# Schematic_MotherBoard.net
KiCad netlist of a schematic drawn in Altium Designer
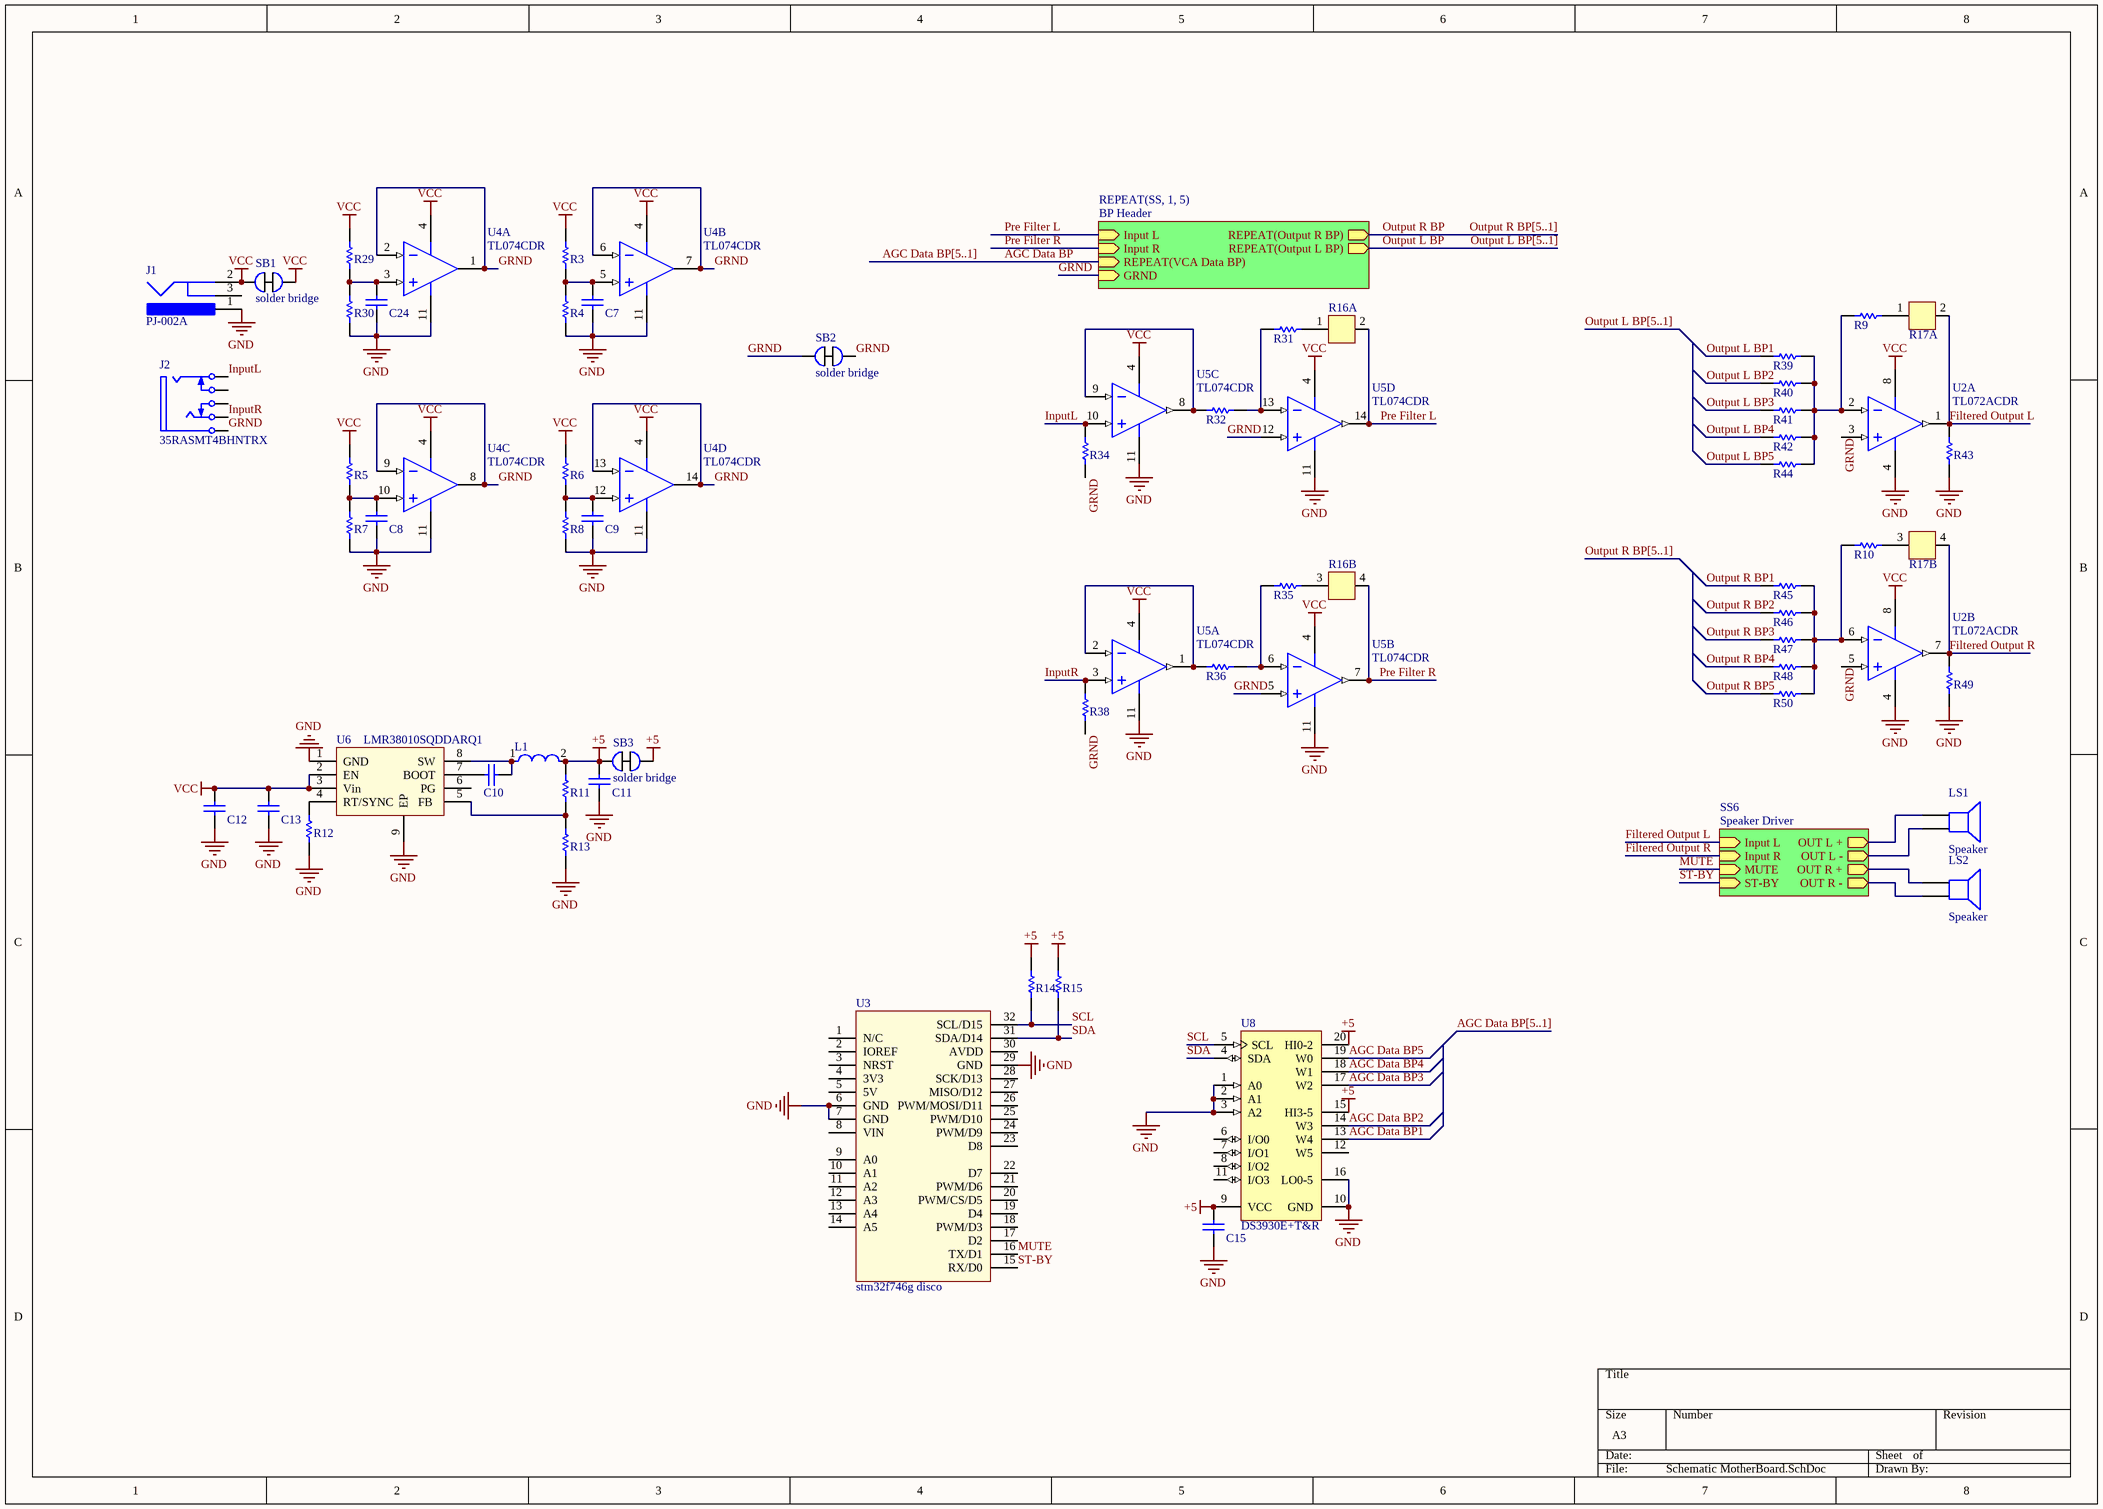
[diagram p0: Schematic MotherBoard.SchDoc]

(export (version "E")
  (design (tool "Eeschema 10.0.6"))
  (components
    (comp (ref "C7")
      (value "1206GC102KAT1A")
      (footprint "AVX-1206-2_L")
      (description "Chip Capacitor, 1 nF, +/- 10%, -55 to 125 degC, 1206 (3216 Metric), RoHS, Tape and Reel")
      (fields (field (name "TOLERANCE") "10%") (field (name "MANUFACTURER") "AVX"))
      (libsource (lib "Altium Content Vault") (part "CAP-NP-2"))
    )
    (comp (ref "C8")
      (value "1206GC102KAT1A")
      (footprint "AVX-1206-2_L")
      (description "Chip Capacitor, 1 nF, +/- 10%, -55 to 125 degC, 1206 (3216 Metric), RoHS, Tape and Reel")
      (fields (field (name "TOLERANCE") "10%") (field (name "MANUFACTURER") "AVX"))
      (libsource (lib "Altium Content Vault") (part "CAP-NP-2"))
    )
    (comp (ref "C9")
      (value "1206GC102KAT1A")
      (footprint "AVX-1206-2_L")
      (description "Chip Capacitor, 1 nF, +/- 10%, -55 to 125 degC, 1206 (3216 Metric), RoHS, Tape and Reel")
      (fields (field (name "TOLERANCE") "10%") (field (name "MANUFACTURER") "AVX"))
      (libsource (lib "Altium Content Vault") (part "CAP-NP-2"))
    )
    (comp (ref "C10")
      (value "1206GC102KAT1A")
      (footprint "AVX-1206-2_L")
      (description "Chip Capacitor, 1 nF, +/- 10%, -55 to 125 degC, 1206 (3216 Metric), RoHS, Tape and Reel")
      (fields (field (name "TOLERANCE") "10%") (field (name "MANUFACTURER") "AVX"))
      (libsource (lib "Altium Content Vault") (part "CAP-NP-2"))
    )
    (comp (ref "C11")
      (value "1206GC102KAT1A")
      (footprint "AVX-1206-2_L")
      (description "Chip Capacitor, 1 nF, +/- 10%, -55 to 125 degC, 1206 (3216 Metric), RoHS, Tape and Reel")
      (fields (field (name "TOLERANCE") "10%") (field (name "MANUFACTURER") "AVX"))
      (libsource (lib "Altium Content Vault") (part "CAP-NP-2"))
    )
    (comp (ref "C12")
      (value "1206GC102KAT1A")
      (footprint "AVX-1206-2_L")
      (description "Chip Capacitor, 1 nF, +/- 10%, -55 to 125 degC, 1206 (3216 Metric), RoHS, Tape and Reel")
      (fields (field (name "TOLERANCE") "10%") (field (name "MANUFACTURER") "AVX"))
      (libsource (lib "Altium Content Vault") (part "CAP-NP-2"))
    )
    (comp (ref "C13")
      (value "1206GC102KAT1A")
      (footprint "AVX-1206-2_L")
      (description "Chip Capacitor, 1 nF, +/- 10%, -55 to 125 degC, 1206 (3216 Metric), RoHS, Tape and Reel")
      (fields (field (name "TOLERANCE") "10%") (field (name "MANUFACTURER") "AVX"))
      (libsource (lib "Altium Content Vault") (part "CAP-NP-2"))
    )
    (comp (ref "C15")
      (value "1206GC102KAT1A")
      (footprint "AVX-1206-2_L")
      (description "Chip Capacitor, 1 nF, +/- 10%, -55 to 125 degC, 1206 (3216 Metric), RoHS, Tape and Reel")
      (fields (field (name "TOLERANCE") "10%") (field (name "MANUFACTURER") "AVX"))
      (libsource (lib "Altium Content Vault") (part "CAP-NP-2"))
    )
    (comp (ref "C24")
      (value "1206GC102KAT1A")
      (footprint "AVX-1206-2_L")
      (description "Chip Capacitor, 1 nF, +/- 10%, -55 to 125 degC, 1206 (3216 Metric), RoHS, Tape and Reel")
      (fields (field (name "TOLERANCE") "10%") (field (name "MANUFACTURER") "AVX"))
      (libsource (lib "Altium Content Vault") (part "CAP-NP-2"))
    )
    (comp (ref "J1")
      (value "PJ-002A")
      (footprint "CUI-PJ-002A_V")
      (fields (field (name "MANUFACTURER") "CUIInc."))
      (libsource (lib "Altium Content Vault") (part "JACK-2CD3-RN_B"))
    )
    (comp (ref "J2")
      (value "35RASMT4BHNTRX")
      (footprint "SWIT-35RASMT4BHNTRX_V")
      (description "Female 3.5 mm Phone Jack, 5 Position, Height 5 mm, RoHS, Tape and Reel")
      (libsource (lib "Altium Content Vault") (part "JACK-3CD5-RN"))
    )
    (comp (ref "L1")
      (value "IHLP5050EZERR56M01")
      (footprint "FP-IHLP-5050EZ-FP_3_226x4-MFG")
      (description "Commercial Inductors, High Saturation Series 0.56uH 36A 1.5mΩ 20%")
      (fields (field (name "TOLERANCE") "20%"))
      (libsource (lib "Altium Content Vault") (part "725321dda6339637d4d059423bc1c3c"))
    )
    (comp (ref "LS1")
      (value "Speaker")
      (footprint "PIN2")
      (description "Loudspeaker")
      (fields (field (name "PUBLISHER") "Altium Limited"))
      (libsource (lib "Miscellaneous Devices") (part "Speaker"))
    )
    (comp (ref "LS2")
      (value "Speaker")
      (footprint "PIN2")
      (description "Loudspeaker")
      (fields (field (name "PUBLISHER") "Altium Limited"))
      (libsource (lib "Miscellaneous Devices") (part "Speaker"))
    )
    (comp (ref "R3")
      (value "ERJ-8GEY0R00V")
      (footprint "RESC3216X70X50NL05T20")
      (fields (field (name "MANUFACTURER") "Panasonic"))
      (libsource (lib "Altium Content Vault") (part "RES"))
    )
    (comp (ref "R4")
      (value "ERJ-8GEY0R00V")
      (footprint "RESC3216X70X50NL05T20")
      (fields (field (name "MANUFACTURER") "Panasonic"))
      (libsource (lib "Altium Content Vault") (part "RES"))
    )
    (comp (ref "R5")
      (value "ERJ-8GEY0R00V")
      (footprint "RESC3216X70X50NL05T20")
      (fields (field (name "MANUFACTURER") "Panasonic"))
      (libsource (lib "Altium Content Vault") (part "RES"))
    )
    (comp (ref "R6")
      (value "ERJ-8GEY0R00V")
      (footprint "RESC3216X70X50NL05T20")
      (fields (field (name "MANUFACTURER") "Panasonic"))
      (libsource (lib "Altium Content Vault") (part "RES"))
    )
    (comp (ref "R7")
      (value "ERJ-8GEY0R00V")
      (footprint "RESC3216X70X50NL05T20")
      (fields (field (name "MANUFACTURER") "Panasonic"))
      (libsource (lib "Altium Content Vault") (part "RES"))
    )
    (comp (ref "R8")
      (value "ERJ-8GEY0R00V")
      (footprint "RESC3216X70X50NL05T20")
      (fields (field (name "MANUFACTURER") "Panasonic"))
      (libsource (lib "Altium Content Vault") (part "RES"))
    )
    (comp (ref "R9")
      (value "ERJ-8GEY0R00V")
      (footprint "RESC3216X70X50NL05T20")
      (fields (field (name "MANUFACTURER") "Panasonic"))
      (libsource (lib "Altium Content Vault") (part "RES"))
    )
    (comp (ref "R10")
      (value "ERJ-8GEY0R00V")
      (footprint "RESC3216X70X50NL05T20")
      (fields (field (name "MANUFACTURER") "Panasonic"))
      (libsource (lib "Altium Content Vault") (part "RES"))
    )
    (comp (ref "R11")
      (value "ERJ-8GEY0R00V")
      (footprint "RESC3216X70X50NL05T20")
      (fields (field (name "MANUFACTURER") "Panasonic"))
      (libsource (lib "Altium Content Vault") (part "RES"))
    )
    (comp (ref "R12")
      (value "ERJ-8GEY0R00V")
      (footprint "RESC3216X70X50NL05T20")
      (fields (field (name "MANUFACTURER") "Panasonic"))
      (libsource (lib "Altium Content Vault") (part "RES"))
    )
    (comp (ref "R13")
      (value "ERJ-8GEY0R00V")
      (footprint "RESC3216X70X50NL05T20")
      (fields (field (name "MANUFACTURER") "Panasonic"))
      (libsource (lib "Altium Content Vault") (part "RES"))
    )
    (comp (ref "R14")
      (value "ERJ-8GEY0R00V")
      (footprint "RESC3216X70X50NL05T20")
      (fields (field (name "MANUFACTURER") "Panasonic"))
      (libsource (lib "Altium Content Vault") (part "RES"))
    )
    (comp (ref "R15")
      (value "ERJ-8GEY0R00V")
      (footprint "RESC3216X70X50NL05T20")
      (fields (field (name "MANUFACTURER") "Panasonic"))
      (libsource (lib "Altium Content Vault") (part "RES"))
    )
    (comp (ref "R16")
      (value "Pot probes")
      (footprint "Pot probe")
      (libsource (lib "Schlib") (part "Pot probes"))
    )
    (comp (ref "R17")
      (value "Pot probes")
      (footprint "Pot probe")
      (libsource (lib "Schlib") (part "Pot probes"))
    )
    (comp (ref "R29")
      (value "ERJ-8GEY0R00V")
      (footprint "RESC3216X70X50NL05T20")
      (fields (field (name "MANUFACTURER") "Panasonic"))
      (libsource (lib "Altium Content Vault") (part "RES"))
    )
    (comp (ref "R30")
      (value "ERJ-8GEY0R00V")
      (footprint "RESC3216X70X50NL05T20")
      (fields (field (name "MANUFACTURER") "Panasonic"))
      (libsource (lib "Altium Content Vault") (part "RES"))
    )
    (comp (ref "R31")
      (value "ERJ-8GEY0R00V")
      (footprint "RESC3216X70X50NL05T20")
      (fields (field (name "MANUFACTURER") "Panasonic"))
      (libsource (lib "Altium Content Vault") (part "RES"))
    )
    (comp (ref "R32")
      (value "ERJ-8GEY0R00V")
      (footprint "RESC3216X70X50NL05T20")
      (fields (field (name "MANUFACTURER") "Panasonic"))
      (libsource (lib "Altium Content Vault") (part "RES"))
    )
    (comp (ref "R34")
      (value "ERJ-8GEY0R00V")
      (footprint "RESC3216X70X50NL05T20")
      (fields (field (name "MANUFACTURER") "Panasonic"))
      (libsource (lib "Altium Content Vault") (part "RES"))
    )
    (comp (ref "R35")
      (value "ERJ-8GEY0R00V")
      (footprint "RESC3216X70X50NL05T20")
      (fields (field (name "MANUFACTURER") "Panasonic"))
      (libsource (lib "Altium Content Vault") (part "RES"))
    )
    (comp (ref "R36")
      (value "ERJ-8GEY0R00V")
      (footprint "RESC3216X70X50NL05T20")
      (fields (field (name "MANUFACTURER") "Panasonic"))
      (libsource (lib "Altium Content Vault") (part "RES"))
    )
    (comp (ref "R38")
      (value "ERJ-8GEY0R00V")
      (footprint "RESC3216X70X50NL05T20")
      (fields (field (name "MANUFACTURER") "Panasonic"))
      (libsource (lib "Altium Content Vault") (part "RES"))
    )
    (comp (ref "R39")
      (value "ERJ-8GEY0R00V")
      (footprint "RESC3216X70X50NL05T20")
      (fields (field (name "MANUFACTURER") "Panasonic"))
      (libsource (lib "Altium Content Vault") (part "RES"))
    )
    (comp (ref "R40")
      (value "ERJ-8GEY0R00V")
      (footprint "RESC3216X70X50NL05T20")
      (fields (field (name "MANUFACTURER") "Panasonic"))
      (libsource (lib "Altium Content Vault") (part "RES"))
    )
    (comp (ref "R41")
      (value "ERJ-8GEY0R00V")
      (footprint "RESC3216X70X50NL05T20")
      (fields (field (name "MANUFACTURER") "Panasonic"))
      (libsource (lib "Altium Content Vault") (part "RES"))
    )
    (comp (ref "R42")
      (value "ERJ-8GEY0R00V")
      (footprint "RESC3216X70X50NL05T20")
      (fields (field (name "MANUFACTURER") "Panasonic"))
      (libsource (lib "Altium Content Vault") (part "RES"))
    )
    (comp (ref "R43")
      (value "ERJ-8GEY0R00V")
      (footprint "RESC3216X70X50NL05T20")
      (fields (field (name "MANUFACTURER") "Panasonic"))
      (libsource (lib "Altium Content Vault") (part "RES"))
    )
    (comp (ref "R44")
      (value "ERJ-8GEY0R00V")
      (footprint "RESC3216X70X50NL05T20")
      (fields (field (name "MANUFACTURER") "Panasonic"))
      (libsource (lib "Altium Content Vault") (part "RES"))
    )
    (comp (ref "R45")
      (value "ERJ-8GEY0R00V")
      (footprint "RESC3216X70X50NL05T20")
      (fields (field (name "MANUFACTURER") "Panasonic"))
      (libsource (lib "Altium Content Vault") (part "RES"))
    )
    (comp (ref "R46")
      (value "ERJ-8GEY0R00V")
      (footprint "RESC3216X70X50NL05T20")
      (fields (field (name "MANUFACTURER") "Panasonic"))
      (libsource (lib "Altium Content Vault") (part "RES"))
    )
    (comp (ref "R47")
      (value "ERJ-8GEY0R00V")
      (footprint "RESC3216X70X50NL05T20")
      (fields (field (name "MANUFACTURER") "Panasonic"))
      (libsource (lib "Altium Content Vault") (part "RES"))
    )
    (comp (ref "R48")
      (value "ERJ-8GEY0R00V")
      (footprint "RESC3216X70X50NL05T20")
      (fields (field (name "MANUFACTURER") "Panasonic"))
      (libsource (lib "Altium Content Vault") (part "RES"))
    )
    (comp (ref "R49")
      (value "ERJ-8GEY0R00V")
      (footprint "RESC3216X70X50NL05T20")
      (fields (field (name "MANUFACTURER") "Panasonic"))
      (libsource (lib "Altium Content Vault") (part "RES"))
    )
    (comp (ref "R50")
      (value "ERJ-8GEY0R00V")
      (footprint "RESC3216X70X50NL05T20")
      (fields (field (name "MANUFACTURER") "Panasonic"))
      (libsource (lib "Altium Content Vault") (part "RES"))
    )
    (comp (ref "SB1")
      (value "solder bridge")
      (footprint "solder bridge")
      (libsource (lib "Schlib") (part "solder bridge"))
    )
    (comp (ref "SB2")
      (value "solder bridge")
      (footprint "solder bridge")
      (libsource (lib "Schlib") (part "solder bridge"))
    )
    (comp (ref "SB3")
      (value "solder bridge")
      (footprint "solder bridge")
      (libsource (lib "Schlib") (part "solder bridge"))
    )
    (comp (ref "U2")
      (value "TL072ACDR")
      (footprint "D0008A_M")
      (fields (field (name "MANUFACTURER") "Texas Instruments"))
      (libsource (lib "Altium Content Vault") (part "TI-AMP-D6-2-8_D"))
    )
    (comp (ref "U3")
      (value "stm32f746g disco")
      (footprint "stm32f746g disco")
      (libsource (lib "Schlib") (part "stm32f746g disco"))
    )
    (comp (ref "U4")
      (value "TL074CDR")
      (footprint "D0014A_N")
      (fields (field (name "MANUFACTURER") "Texas Instruments"))
      (libsource (lib "Altium Content Vault") (part "TI-TLXX4X_MC3403-X14"))
    )
    (comp (ref "U5")
      (value "TL074CDR")
      (footprint "D0014A_N")
      (fields (field (name "MANUFACTURER") "Texas Instruments"))
      (libsource (lib "Altium Content Vault") (part "TI-TLXX4X_MC3403-X14"))
    )
    (comp (ref "U6")
      (value "LMR38010SQDDARQ1")
      (footprint "LMR38010SQDDARQ1")
      (libsource (lib "Schlib") (part "LMR38010SQDDARQ1"))
    )
    (comp (ref "U8")
      (value "DS3930E+T&R")
      (footprint "MAXM-U20+5_L")
      (libsource (lib "Altium Content Vault") (part "DS3930-U20X5"))
    )
  )
  (nets
    (net (code "1") (name "+5") (class "Default")
      (node (ref "C11") (pin "2") (pinfunction "2_2") (pintype "passive"))
      (node (ref "C15") (pin "2") (pinfunction "2_2") (pintype "passive"))
      (node (ref "L1") (pin "2") (pinfunction "2_2") (pintype "passive"))
      (node (ref "R11") (pin "2") (pinfunction "2_2") (pintype "passive"))
      (node (ref "R14") (pin "2") (pinfunction "2_2") (pintype "passive"))
      (node (ref "R15") (pin "2") (pinfunction "2_2") (pintype "passive"))
      (node (ref "SB3") (pin "1") (pinfunction "1_1") (pintype "passive"))
      (node (ref "SB3") (pin "2") (pinfunction "2_2") (pintype "passive"))
      (node (ref "U8") (pin "15") (pinfunction "HI3-5_15") (pintype "passive"))
      (node (ref "U8") (pin "20") (pinfunction "HI0-2_20") (pintype "passive"))
      (node (ref "U8") (pin "9") (pinfunction "VCC_9") (pintype "power_in"))
    )
    (net (code "3") (name "/AGC Data BP1") (class "Default")
      (node (ref "U8") (pin "13") (pinfunction "W4_13") (pintype "passive"))
    )
    (net (code "4") (name "/AGC Data BP2") (class "Default")
      (node (ref "U8") (pin "14") (pinfunction "W3_14") (pintype "passive"))
    )
    (net (code "5") (name "/AGC Data BP3") (class "Default")
      (node (ref "U8") (pin "17") (pinfunction "W2_17") (pintype "passive"))
    )
    (net (code "6") (name "/AGC Data BP4") (class "Default")
      (node (ref "U8") (pin "18") (pinfunction "W1_18") (pintype "passive"))
    )
    (net (code "7") (name "/AGC Data BP5") (class "Default")
      (node (ref "U8") (pin "19") (pinfunction "W0_19") (pintype "passive"))
    )
    (net (code "8") (name "/Filtered Output L") (class "Default")
      (node (ref "R17") (pin "2") (pinfunction "2_2") (pintype "passive"))
      (node (ref "R43") (pin "1") (pinfunction "1_1") (pintype "passive"))
      (node (ref "U2") (pin "1") (pinfunction "OUT1_1") (pintype "output"))
    )
    (net (code "9") (name "/Filtered Output R") (class "Default")
      (node (ref "R17") (pin "4") (pinfunction "4_4") (pintype "passive"))
      (node (ref "R49") (pin "1") (pinfunction "1_1") (pintype "passive"))
      (node (ref "U2") (pin "7") (pinfunction "OUT2_7") (pintype "output"))
    )
    (net (code "10") (name "/GRND") (class "Default")
      (node (ref "J2") (pin "1") (pinfunction "1_1") (pintype "passive"))
      (node (ref "R34") (pin "2") (pinfunction "2_2") (pintype "passive"))
      (node (ref "R38") (pin "2") (pinfunction "2_2") (pintype "passive"))
      (node (ref "SB2") (pin "1") (pinfunction "1_1") (pintype "passive"))
      (node (ref "SB2") (pin "2") (pinfunction "2_2") (pintype "passive"))
      (node (ref "U2") (pin "3") (pinfunction "IN1+_3") (pintype "input"))
      (node (ref "U2") (pin "5") (pinfunction "IN2+_5") (pintype "input"))
      (node (ref "U4") (pin "1") (pinfunction "OUT1_1") (pintype "output"))
      (node (ref "U4") (pin "13") (pinfunction "IN4-_13") (pintype "input"))
      (node (ref "U4") (pin "14") (pinfunction "OUT4_14") (pintype "output"))
      (node (ref "U4") (pin "2") (pinfunction "IN1-_2") (pintype "input"))
      (node (ref "U4") (pin "6") (pinfunction "IN2-_6") (pintype "input"))
      (node (ref "U4") (pin "7") (pinfunction "OUT2_7") (pintype "output"))
      (node (ref "U4") (pin "8") (pinfunction "OUT3_8") (pintype "output"))
      (node (ref "U4") (pin "9") (pinfunction "IN3-_9") (pintype "input"))
      (node (ref "U5") (pin "12") (pinfunction "IN4+_12") (pintype "input"))
      (node (ref "U5") (pin "5") (pinfunction "IN2+_5") (pintype "input"))
    )
    (net (code "11") (name "/InputL") (class "Default")
      (node (ref "J2") (pin "2") (pinfunction "2_2") (pintype "passive"))
      (node (ref "R34") (pin "1") (pinfunction "1_1") (pintype "passive"))
      (node (ref "U5") (pin "10") (pinfunction "IN3+_10") (pintype "input"))
    )
    (net (code "12") (name "/InputR") (class "Default")
      (node (ref "J2") (pin "3") (pinfunction "3_3") (pintype "passive"))
      (node (ref "R38") (pin "1") (pinfunction "1_1") (pintype "passive"))
      (node (ref "U5") (pin "3") (pinfunction "IN1+_3") (pintype "input"))
    )
    (net (code "13") (name "/MUTE") (class "Default")
      (node (ref "U3") (pin "16") (pinfunction "TX/D1_16") (pintype "passive"))
    )
    (net (code "14") (name "/OUT L +") (class "Default")
      (node (ref "LS1") (pin "1") (pinfunction "1_1") (pintype "passive"))
    )
    (net (code "15") (name "/OUT L -") (class "Default")
      (node (ref "LS1") (pin "2") (pinfunction "2_2") (pintype "passive"))
    )
    (net (code "16") (name "/OUT R +") (class "Default")
      (node (ref "LS2") (pin "2") (pinfunction "2_2") (pintype "passive"))
    )
    (net (code "17") (name "/OUT R -") (class "Default")
      (node (ref "LS2") (pin "1") (pinfunction "1_1") (pintype "passive"))
    )
    (net (code "19") (name "/Output L BP1") (class "Default")
      (node (ref "R39") (pin "1") (pinfunction "1_1") (pintype "passive"))
    )
    (net (code "20") (name "/Output L BP2") (class "Default")
      (node (ref "R40") (pin "1") (pinfunction "1_1") (pintype "passive"))
    )
    (net (code "21") (name "/Output L BP3") (class "Default")
      (node (ref "R41") (pin "1") (pinfunction "1_1") (pintype "passive"))
    )
    (net (code "22") (name "/Output L BP4") (class "Default")
      (node (ref "R42") (pin "1") (pinfunction "1_1") (pintype "passive"))
    )
    (net (code "23") (name "/Output L BP5") (class "Default")
      (node (ref "R44") (pin "1") (pinfunction "1_1") (pintype "passive"))
    )
    (net (code "25") (name "/Output R BP1") (class "Default")
      (node (ref "R45") (pin "1") (pinfunction "1_1") (pintype "passive"))
    )
    (net (code "26") (name "/Output R BP2") (class "Default")
      (node (ref "R46") (pin "1") (pinfunction "1_1") (pintype "passive"))
    )
    (net (code "27") (name "/Output R BP3") (class "Default")
      (node (ref "R47") (pin "1") (pinfunction "1_1") (pintype "passive"))
    )
    (net (code "28") (name "/Output R BP4") (class "Default")
      (node (ref "R48") (pin "1") (pinfunction "1_1") (pintype "passive"))
    )
    (net (code "29") (name "/Output R BP5") (class "Default")
      (node (ref "R50") (pin "1") (pinfunction "1_1") (pintype "passive"))
    )
    (net (code "30") (name "/Pre Filter L") (class "Default")
      (node (ref "R16") (pin "2") (pinfunction "2_2") (pintype "passive"))
      (node (ref "U5") (pin "14") (pinfunction "OUT4_14") (pintype "output"))
    )
    (net (code "31") (name "/Pre Filter R") (class "Default")
      (node (ref "R16") (pin "4") (pinfunction "4_4") (pintype "passive"))
      (node (ref "U5") (pin "7") (pinfunction "OUT2_7") (pintype "output"))
    )
    (net (code "32") (name "/SCL") (class "Default")
      (node (ref "R14") (pin "1") (pinfunction "1_1") (pintype "passive"))
      (node (ref "U3") (pin "32") (pinfunction "SCL/D15_32") (pintype "passive"))
      (node (ref "U8") (pin "5") (pinfunction "SCL_5") (pintype "input"))
    )
    (net (code "33") (name "/SDA") (class "Default")
      (node (ref "R15") (pin "1") (pinfunction "1_1") (pintype "passive"))
      (node (ref "U3") (pin "31") (pinfunction "SDA/D14_31") (pintype "passive"))
      (node (ref "U8") (pin "4") (pinfunction "SDA_4") (pintype "bidirectional"))
    )
    (net (code "34") (name "/ST-BY") (class "Default")
      (node (ref "U3") (pin "15") (pinfunction "RX/D0_15") (pintype "passive"))
    )
    (net (code "38") (name "GND") (class "Default")
      (node (ref "C11") (pin "1") (pinfunction "1_1") (pintype "passive"))
      (node (ref "C12") (pin "1") (pinfunction "1_1") (pintype "passive"))
      (node (ref "C13") (pin "1") (pinfunction "1_1") (pintype "passive"))
      (node (ref "C15") (pin "1") (pinfunction "1_1") (pintype "passive"))
      (node (ref "C24") (pin "1") (pinfunction "1_1") (pintype "passive"))
      (node (ref "C7") (pin "1") (pinfunction "1_1") (pintype "passive"))
      (node (ref "C8") (pin "1") (pinfunction "1_1") (pintype "passive"))
      (node (ref "C9") (pin "1") (pinfunction "1_1") (pintype "passive"))
      (node (ref "J1") (pin "1") (pinfunction "1_1") (pintype "passive"))
      (node (ref "R12") (pin "1") (pinfunction "1_1") (pintype "passive"))
      (node (ref "R13") (pin "1") (pinfunction "1_1") (pintype "passive"))
      (node (ref "R30") (pin "1") (pinfunction "1_1") (pintype "passive"))
      (node (ref "R4") (pin "1") (pinfunction "1_1") (pintype "passive"))
      (node (ref "R43") (pin "2") (pinfunction "2_2") (pintype "passive"))
      (node (ref "R49") (pin "2") (pinfunction "2_2") (pintype "passive"))
      (node (ref "R7") (pin "1") (pinfunction "1_1") (pintype "passive"))
      (node (ref "R8") (pin "1") (pinfunction "1_1") (pintype "passive"))
      (node (ref "U2") (pin "4") (pinfunction "VCC-_4") (pintype "power_in"))
      (node (ref "U3") (pin "29") (pinfunction "GND_29") (pintype "passive"))
      (node (ref "U3") (pin "6") (pinfunction "GND_6") (pintype "passive"))
      (node (ref "U3") (pin "7") (pinfunction "GND_7") (pintype "passive"))
      (node (ref "U4") (pin "11") (pinfunction "VCC-_11") (pintype "power_in"))
      (node (ref "U5") (pin "11") (pinfunction "VCC-_11") (pintype "power_in"))
      (node (ref "U6") (pin "1") (pinfunction "GND_1") (pintype "passive"))
      (node (ref "U6") (pin "9") (pinfunction "EP_9") (pintype "passive"))
      (node (ref "U8") (pin "1") (pinfunction "A0_1") (pintype "input"))
      (node (ref "U8") (pin "10") (pinfunction "GND_10") (pintype "power_in"))
      (node (ref "U8") (pin "16") (pinfunction "LO0-5_16") (pintype "passive"))
      (node (ref "U8") (pin "2") (pinfunction "A1_2") (pintype "input"))
      (node (ref "U8") (pin "3") (pinfunction "A2_3") (pintype "input"))
    )
    (net (code "39") (name "Net-(R10-Pad2)") (class "Default")
      (node (ref "R10") (pin "2") (pinfunction "2_2") (pintype "passive"))
      (node (ref "R17") (pin "3") (pinfunction "3_3") (pintype "passive"))
    )
    (net (code "40") (name "Net-(R16-Pad1)") (class "Default")
      (node (ref "R16") (pin "1") (pinfunction "1_1") (pintype "passive"))
      (node (ref "R31") (pin "2") (pinfunction "2_2") (pintype "passive"))
    )
    (net (code "41") (name "Net-(R16-Pad3)") (class "Default")
      (node (ref "R16") (pin "3") (pinfunction "3_3") (pintype "passive"))
      (node (ref "R35") (pin "2") (pinfunction "2_2") (pintype "passive"))
    )
    (net (code "42") (name "Net-(R17-Pad1)") (class "Default")
      (node (ref "R17") (pin "1") (pinfunction "1_1") (pintype "passive"))
      (node (ref "R9") (pin "2") (pinfunction "2_2") (pintype "passive"))
    )
    (net (code "43") (name "Net-(U2A-IN1-)") (class "Default")
      (node (ref "R39") (pin "2") (pinfunction "2_2") (pintype "passive"))
      (node (ref "R40") (pin "2") (pinfunction "2_2") (pintype "passive"))
      (node (ref "R41") (pin "2") (pinfunction "2_2") (pintype "passive"))
      (node (ref "R42") (pin "2") (pinfunction "2_2") (pintype "passive"))
      (node (ref "R44") (pin "2") (pinfunction "2_2") (pintype "passive"))
      (node (ref "R9") (pin "1") (pinfunction "1_1") (pintype "passive"))
      (node (ref "U2") (pin "2") (pinfunction "IN1-_2") (pintype "input"))
    )
    (net (code "44") (name "Net-(U2B-IN2-)") (class "Default")
      (node (ref "R10") (pin "1") (pinfunction "1_1") (pintype "passive"))
      (node (ref "R45") (pin "2") (pinfunction "2_2") (pintype "passive"))
      (node (ref "R46") (pin "2") (pinfunction "2_2") (pintype "passive"))
      (node (ref "R47") (pin "2") (pinfunction "2_2") (pintype "passive"))
      (node (ref "R48") (pin "2") (pinfunction "2_2") (pintype "passive"))
      (node (ref "R50") (pin "2") (pinfunction "2_2") (pintype "passive"))
      (node (ref "U2") (pin "6") (pinfunction "IN2-_6") (pintype "input"))
    )
    (net (code "45") (name "Net-(U4A-IN1+)") (class "Default")
      (node (ref "C24") (pin "2") (pinfunction "2_2") (pintype "passive"))
      (node (ref "R29") (pin "2") (pinfunction "2_2") (pintype "passive"))
      (node (ref "R30") (pin "2") (pinfunction "2_2") (pintype "passive"))
      (node (ref "U4") (pin "3") (pinfunction "IN1+_3") (pintype "input"))
    )
    (net (code "46") (name "Net-(U4B-IN2+)") (class "Default")
      (node (ref "C7") (pin "2") (pinfunction "2_2") (pintype "passive"))
      (node (ref "R3") (pin "2") (pinfunction "2_2") (pintype "passive"))
      (node (ref "R4") (pin "2") (pinfunction "2_2") (pintype "passive"))
      (node (ref "U4") (pin "5") (pinfunction "IN2+_5") (pintype "input"))
    )
    (net (code "47") (name "Net-(U4C-IN3+)") (class "Default")
      (node (ref "C8") (pin "2") (pinfunction "2_2") (pintype "passive"))
      (node (ref "R5") (pin "2") (pinfunction "2_2") (pintype "passive"))
      (node (ref "R7") (pin "2") (pinfunction "2_2") (pintype "passive"))
      (node (ref "U4") (pin "10") (pinfunction "IN3+_10") (pintype "input"))
    )
    (net (code "48") (name "Net-(U4D-IN4+)") (class "Default")
      (node (ref "C9") (pin "2") (pinfunction "2_2") (pintype "passive"))
      (node (ref "R6") (pin "2") (pinfunction "2_2") (pintype "passive"))
      (node (ref "R8") (pin "2") (pinfunction "2_2") (pintype "passive"))
      (node (ref "U4") (pin "12") (pinfunction "IN4+_12") (pintype "input"))
    )
    (net (code "49") (name "Net-(U5A-IN1-)") (class "Default")
      (node (ref "R36") (pin "1") (pinfunction "1_1") (pintype "passive"))
      (node (ref "U5") (pin "1") (pinfunction "OUT1_1") (pintype "output"))
      (node (ref "U5") (pin "2") (pinfunction "IN1-_2") (pintype "input"))
    )
    (net (code "50") (name "Net-(U5B-IN2-)") (class "Default")
      (node (ref "R35") (pin "1") (pinfunction "1_1") (pintype "passive"))
      (node (ref "R36") (pin "2") (pinfunction "2_2") (pintype "passive"))
      (node (ref "U5") (pin "6") (pinfunction "IN2-_6") (pintype "input"))
    )
    (net (code "51") (name "Net-(U5C-IN3-)") (class "Default")
      (node (ref "R32") (pin "1") (pinfunction "1_1") (pintype "passive"))
      (node (ref "U5") (pin "8") (pinfunction "OUT3_8") (pintype "output"))
      (node (ref "U5") (pin "9") (pinfunction "IN3-_9") (pintype "input"))
    )
    (net (code "52") (name "Net-(U5D-IN4-)") (class "Default")
      (node (ref "R31") (pin "1") (pinfunction "1_1") (pintype "passive"))
      (node (ref "R32") (pin "2") (pinfunction "2_2") (pintype "passive"))
      (node (ref "U5") (pin "13") (pinfunction "IN4-_13") (pintype "input"))
    )
    (net (code "53") (name "Net-(U6-BOOT)") (class "Default")
      (node (ref "C10") (pin "2") (pinfunction "2_2") (pintype "passive"))
      (node (ref "U6") (pin "7") (pinfunction "BOOT_7") (pintype "passive"))
    )
    (net (code "54") (name "Net-(U6-FB)") (class "Default")
      (node (ref "R11") (pin "1") (pinfunction "1_1") (pintype "passive"))
      (node (ref "R13") (pin "2") (pinfunction "2_2") (pintype "passive"))
      (node (ref "U6") (pin "5") (pinfunction "FB_5") (pintype "passive"))
    )
    (net (code "55") (name "Net-(U6-RT{slash}SYNC)") (class "Default")
      (node (ref "R12") (pin "2") (pinfunction "2_2") (pintype "passive"))
      (node (ref "U6") (pin "4") (pinfunction "RT/SYNC_4") (pintype "passive"))
    )
    (net (code "56") (name "Net-(U6-SW)") (class "Default")
      (node (ref "C10") (pin "1") (pinfunction "1_1") (pintype "passive"))
      (node (ref "L1") (pin "1") (pinfunction "1_1") (pintype "passive"))
      (node (ref "U6") (pin "8") (pinfunction "SW_8") (pintype "passive"))
    )
    (net (code "57") (name "VCC") (class "Default")
      (node (ref "C12") (pin "2") (pinfunction "2_2") (pintype "passive"))
      (node (ref "C13") (pin "2") (pinfunction "2_2") (pintype "passive"))
      (node (ref "J1") (pin "2") (pinfunction "2_2") (pintype "passive"))
      (node (ref "R29") (pin "1") (pinfunction "1_1") (pintype "passive"))
      (node (ref "R3") (pin "1") (pinfunction "1_1") (pintype "passive"))
      (node (ref "R5") (pin "1") (pinfunction "1_1") (pintype "passive"))
      (node (ref "R6") (pin "1") (pinfunction "1_1") (pintype "passive"))
      (node (ref "SB1") (pin "1") (pinfunction "1_1") (pintype "passive"))
      (node (ref "SB1") (pin "2") (pinfunction "2_2") (pintype "passive"))
      (node (ref "U2") (pin "8") (pinfunction "VCC+_8") (pintype "power_in"))
      (node (ref "U4") (pin "4") (pinfunction "VCC+_4") (pintype "power_in"))
      (node (ref "U5") (pin "4") (pinfunction "VCC+_4") (pintype "power_in"))
      (node (ref "U6") (pin "2") (pinfunction "EN_2") (pintype "passive"))
      (node (ref "U6") (pin "3") (pinfunction "Vin_3") (pintype "passive"))
    )
    (net (code "58") (name "unconnected-(J1-Pad3)") (class "Default")
      (node (ref "J1") (pin "3") (pinfunction "3_3") (pintype "passive"))
    )
    (net (code "59") (name "unconnected-(J2-Pad4)") (class "Default")
      (node (ref "J2") (pin "4") (pinfunction "4_4") (pintype "passive"))
    )
    (net (code "60") (name "unconnected-(J2-Pad5)") (class "Default")
      (node (ref "J2") (pin "5") (pinfunction "5_5") (pintype "passive"))
    )
    (net (code "61") (name "unconnected-(U3-3V3-Pad4)") (class "Default")
      (node (ref "U3") (pin "4") (pinfunction "3V3_4") (pintype "passive"))
    )
    (net (code "62") (name "unconnected-(U3-5V-Pad5)") (class "Default")
      (node (ref "U3") (pin "5") (pinfunction "5V_5") (pintype "passive"))
    )
    (net (code "63") (name "unconnected-(U3-A0-Pad9)") (class "Default")
      (node (ref "U3") (pin "9") (pinfunction "A0_9") (pintype "passive"))
    )
    (net (code "64") (name "unconnected-(U3-A1-Pad10)") (class "Default")
      (node (ref "U3") (pin "10") (pinfunction "A1_10") (pintype "passive"))
    )
    (net (code "65") (name "unconnected-(U3-A2-Pad11)") (class "Default")
      (node (ref "U3") (pin "11") (pinfunction "A2_11") (pintype "passive"))
    )
    (net (code "66") (name "unconnected-(U3-A3-Pad12)") (class "Default")
      (node (ref "U3") (pin "12") (pinfunction "A3_12") (pintype "passive"))
    )
    (net (code "67") (name "unconnected-(U3-A4-Pad13)") (class "Default")
      (node (ref "U3") (pin "13") (pinfunction "A4_13") (pintype "passive"))
    )
    (net (code "68") (name "unconnected-(U3-A5-Pad14)") (class "Default")
      (node (ref "U3") (pin "14") (pinfunction "A5_14") (pintype "passive"))
    )
    (net (code "69") (name "unconnected-(U3-AVDD-Pad30)") (class "Default")
      (node (ref "U3") (pin "30") (pinfunction "AVDD_30") (pintype "passive"))
    )
    (net (code "70") (name "unconnected-(U3-D2-Pad17)") (class "Default")
      (node (ref "U3") (pin "17") (pinfunction "D2_17") (pintype "passive"))
    )
    (net (code "71") (name "unconnected-(U3-D4-Pad19)") (class "Default")
      (node (ref "U3") (pin "19") (pinfunction "D4_19") (pintype "passive"))
    )
    (net (code "72") (name "unconnected-(U3-D7-Pad22)") (class "Default")
      (node (ref "U3") (pin "22") (pinfunction "D7_22") (pintype "passive"))
    )
    (net (code "73") (name "unconnected-(U3-D8-Pad23)") (class "Default")
      (node (ref "U3") (pin "23") (pinfunction "D8_23") (pintype "passive"))
    )
    (net (code "74") (name "unconnected-(U3-IOREF-Pad2)") (class "Default")
      (node (ref "U3") (pin "2") (pinfunction "IOREF_2") (pintype "passive"))
    )
    (net (code "75") (name "unconnected-(U3-MISO{slash}D12-Pad27)") (class "Default")
      (node (ref "U3") (pin "27") (pinfunction "MISO/D12_27") (pintype "passive"))
    )
    (net (code "76") (name "unconnected-(U3-NRST-Pad3)") (class "Default")
      (node (ref "U3") (pin "3") (pinfunction "NRST_3") (pintype "passive"))
    )
    (net (code "77") (name "unconnected-(U3-N{slash}C-Pad1)") (class "Default")
      (node (ref "U3") (pin "1") (pinfunction "N/C_1") (pintype "passive"))
    )
    (net (code "78") (name "unconnected-(U3-PWM{slash}CS{slash}D5-Pad20)") (class "Default")
      (node (ref "U3") (pin "20") (pinfunction "PWM/CS/D5_20") (pintype "passive"))
    )
    (net (code "79") (name "unconnected-(U3-PWM{slash}D3-Pad18)") (class "Default")
      (node (ref "U3") (pin "18") (pinfunction "PWM/D3_18") (pintype "passive"))
    )
    (net (code "80") (name "unconnected-(U3-PWM{slash}D6-Pad21)") (class "Default")
      (node (ref "U3") (pin "21") (pinfunction "PWM/D6_21") (pintype "passive"))
    )
    (net (code "81") (name "unconnected-(U3-PWM{slash}D9-Pad24)") (class "Default")
      (node (ref "U3") (pin "24") (pinfunction "PWM/D9_24") (pintype "passive"))
    )
    (net (code "82") (name "unconnected-(U3-PWM{slash}D10-Pad25)") (class "Default")
      (node (ref "U3") (pin "25") (pinfunction "PWM/D10_25") (pintype "passive"))
    )
    (net (code "83") (name "unconnected-(U3-PWM{slash}MOSI{slash}D11-Pad26)") (class "Default")
      (node (ref "U3") (pin "26") (pinfunction "PWM/MOSI/D11_26") (pintype "passive"))
    )
    (net (code "84") (name "unconnected-(U3-SCK{slash}D13-Pad28)") (class "Default")
      (node (ref "U3") (pin "28") (pinfunction "SCK/D13_28") (pintype "passive"))
    )
    (net (code "85") (name "unconnected-(U3-VIN-Pad8)") (class "Default")
      (node (ref "U3") (pin "8") (pinfunction "VIN_8") (pintype "passive"))
    )
    (net (code "86") (name "unconnected-(U6-PG-Pad6)") (class "Default")
      (node (ref "U6") (pin "6") (pinfunction "PG_6") (pintype "passive"))
    )
    (net (code "87") (name "unconnected-(U8-I{slash}O0-Pad6)") (class "Default")
      (node (ref "U8") (pin "6") (pinfunction "I/O0_6") (pintype "bidirectional"))
    )
    (net (code "88") (name "unconnected-(U8-I{slash}O1-Pad7)") (class "Default")
      (node (ref "U8") (pin "7") (pinfunction "I/O1_7") (pintype "bidirectional"))
    )
    (net (code "89") (name "unconnected-(U8-I{slash}O2-Pad8)") (class "Default")
      (node (ref "U8") (pin "8") (pinfunction "I/O2_8") (pintype "bidirectional"))
    )
    (net (code "90") (name "unconnected-(U8-I{slash}O3-Pad11)") (class "Default")
      (node (ref "U8") (pin "11") (pinfunction "I/O3_11") (pintype "bidirectional"))
    )
    (net (code "91") (name "unconnected-(U8-W5-Pad12)") (class "Default")
      (node (ref "U8") (pin "12") (pinfunction "W5_12") (pintype "passive"))
    )
  )
)
